# Connector_Card2.net
KiCad netlist of a schematic drawn in Altium Designer
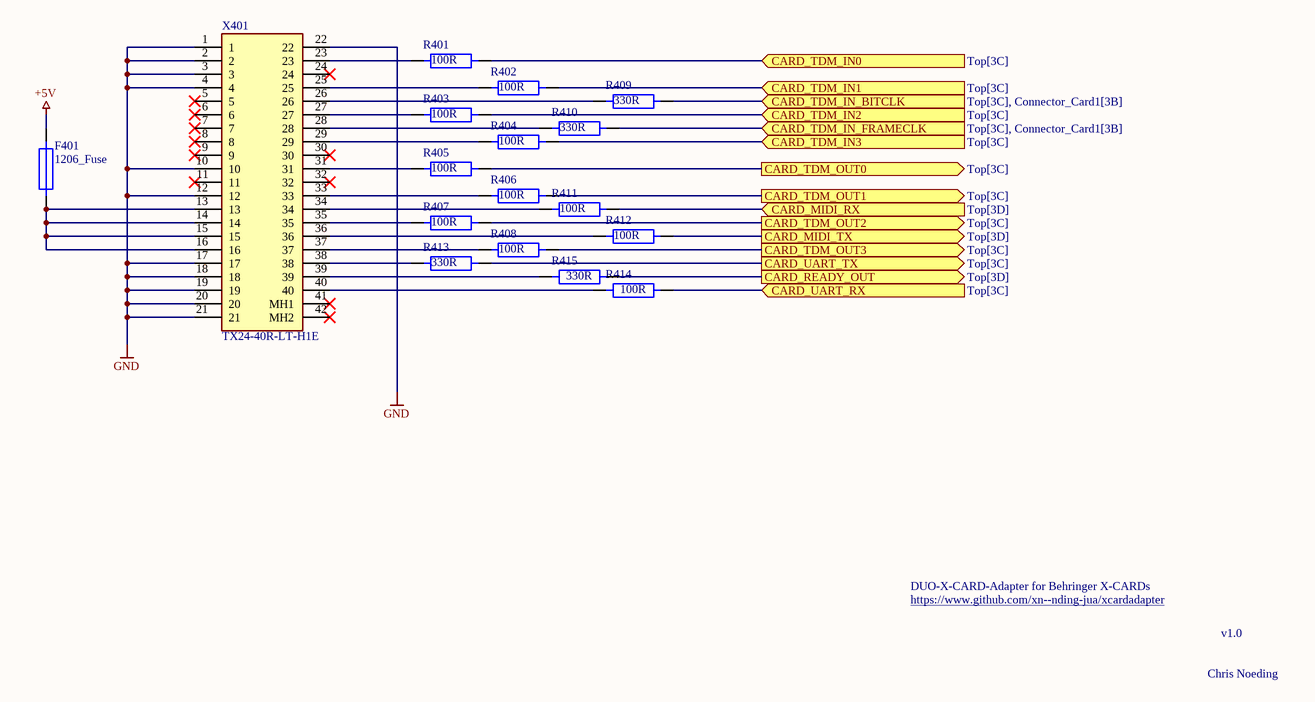
[diagram p0: Connector_Card2.SchDoc]

(export (version "E")
  (design (tool "Eeschema 10.0.6"))
  (components
    (comp (ref "F401")
      (value "1206_Fuse")
      (footprint "1206")
      (libsource (lib "FPGA_Board_Library") (part "1206_Fuse"))
    )
    (comp (ref "R401")
      (value "100R")
      (footprint "1206")
      (description "1206_R")
      (libsource (lib "FPGA_Board_Library") (part "1206_R"))
    )
    (comp (ref "R402")
      (value "100R")
      (footprint "1206")
      (description "1206_R")
      (libsource (lib "FPGA_Board_Library") (part "1206_R"))
    )
    (comp (ref "R403")
      (value "100R")
      (footprint "1206")
      (description "1206_R")
      (libsource (lib "FPGA_Board_Library") (part "1206_R"))
    )
    (comp (ref "R404")
      (value "100R")
      (footprint "1206")
      (description "1206_R")
      (libsource (lib "FPGA_Board_Library") (part "1206_R"))
    )
    (comp (ref "R405")
      (value "100R")
      (footprint "1206")
      (description "330R")
      (libsource (lib "FPGA_Board_Library") (part "1206_R"))
    )
    (comp (ref "R406")
      (value "100R")
      (footprint "1206")
      (description "330R")
      (libsource (lib "FPGA_Board_Library") (part "1206_R"))
    )
    (comp (ref "R407")
      (value "100R")
      (footprint "1206")
      (description "1206_R")
      (libsource (lib "FPGA_Board_Library") (part "1206_R"))
    )
    (comp (ref "R408")
      (value "100R")
      (footprint "1206")
      (description "1206_R")
      (libsource (lib "FPGA_Board_Library") (part "1206_R"))
    )
    (comp (ref "R409")
      (value "330R")
      (footprint "1206")
      (description "1206_R")
      (libsource (lib "FPGA_Board_Library") (part "1206_R"))
    )
    (comp (ref "R410")
      (value "330R")
      (footprint "1206")
      (description "1206_R")
      (libsource (lib "FPGA_Board_Library") (part "1206_R"))
    )
    (comp (ref "R411")
      (value "100R")
      (footprint "1206")
      (description "1206_R")
      (libsource (lib "FPGA_Board_Library") (part "1206_R"))
    )
    (comp (ref "R412")
      (value "100R")
      (footprint "1206")
      (description "1206_R")
      (libsource (lib "FPGA_Board_Library") (part "1206_R"))
    )
    (comp (ref "R413")
      (value "330R")
      (footprint "1206")
      (description "1206_R")
      (libsource (lib "FPGA_Board_Library") (part "1206_R"))
    )
    (comp (ref "R414")
      (value "100R")
      (footprint "1206")
      (description "1206_R")
      (libsource (lib "FPGA_Board_Library") (part "1206_R"))
    )
    (comp (ref "R415")
      (value "330R")
      (footprint "1206")
      (description "1206_R")
      (libsource (lib "FPGA_Board_Library") (part "1206_R"))
    )
    (comp (ref "X401")
      (value "TX24-40R-LT-H1E")
      (footprint "SamacSys:TX2440RLTH1E")
      (description "Connector")
      (fields (field (name "MOUSER PART NUMBER") "656-TX24-40R-LT-H1E"))
      (libsource (lib "*") (part "TX24-40R-LT-H1E"))
    )
  )
  (nets
    (net (code "1") (name "+5V") (class "Default")
      (node (ref "F401") (pin "2") (pinfunction "2_2") (pintype "passive"))
    )
    (net (code "2") (name "/CARD_MIDI_RX") (class "Default")
      (node (ref "R411") (pin "2") (pinfunction "2_2") (pintype "passive"))
    )
    (net (code "3") (name "/CARD_MIDI_TX") (class "Default")
      (node (ref "R412") (pin "2") (pinfunction "2_2") (pintype "passive"))
    )
    (net (code "4") (name "/CARD_READY_OUT") (class "Default")
      (node (ref "R415") (pin "2") (pinfunction "2_2") (pintype "passive"))
    )
    (net (code "5") (name "/CARD_TDM_IN0") (class "Default")
      (node (ref "R401") (pin "2") (pinfunction "2_2") (pintype "passive"))
    )
    (net (code "6") (name "/CARD_TDM_IN1") (class "Default")
      (node (ref "R402") (pin "2") (pinfunction "2_2") (pintype "passive"))
    )
    (net (code "7") (name "/CARD_TDM_IN2") (class "Default")
      (node (ref "R403") (pin "2") (pinfunction "2_2") (pintype "passive"))
    )
    (net (code "8") (name "/CARD_TDM_IN3") (class "Default")
      (node (ref "R404") (pin "2") (pinfunction "2_2") (pintype "passive"))
    )
    (net (code "9") (name "/CARD_TDM_IN_BITCLK") (class "Default")
      (node (ref "R409") (pin "2") (pinfunction "2_2") (pintype "passive"))
    )
    (net (code "10") (name "/CARD_TDM_IN_FRAMECLK") (class "Default")
      (node (ref "R410") (pin "2") (pinfunction "2_2") (pintype "passive"))
    )
    (net (code "11") (name "/CARD_TDM_OUT0") (class "Default")
      (node (ref "R405") (pin "2") (pinfunction "2_2") (pintype "passive"))
    )
    (net (code "12") (name "/CARD_TDM_OUT1") (class "Default")
      (node (ref "R406") (pin "2") (pinfunction "2_2") (pintype "passive"))
    )
    (net (code "13") (name "/CARD_TDM_OUT2") (class "Default")
      (node (ref "R407") (pin "2") (pinfunction "2_2") (pintype "passive"))
    )
    (net (code "14") (name "/CARD_TDM_OUT3") (class "Default")
      (node (ref "R408") (pin "2") (pinfunction "2_2") (pintype "passive"))
    )
    (net (code "15") (name "/CARD_UART_RX") (class "Default")
      (node (ref "R414") (pin "2") (pinfunction "2_2") (pintype "passive"))
    )
    (net (code "16") (name "/CARD_UART_TX") (class "Default")
      (node (ref "R413") (pin "2") (pinfunction "2_2") (pintype "passive"))
    )
    (net (code "17") (name "GND") (class "Default")
      (node (ref "X401") (pin "1") (pinfunction "1_1") (pintype "passive"))
      (node (ref "X401") (pin "10") (pinfunction "10_10") (pintype "passive"))
      (node (ref "X401") (pin "12") (pinfunction "12_12") (pintype "passive"))
      (node (ref "X401") (pin "17") (pinfunction "17_17") (pintype "passive"))
      (node (ref "X401") (pin "18") (pinfunction "18_18") (pintype "passive"))
      (node (ref "X401") (pin "19") (pinfunction "19_19") (pintype "passive"))
      (node (ref "X401") (pin "2") (pinfunction "2_2") (pintype "passive"))
      (node (ref "X401") (pin "20") (pinfunction "20_20") (pintype "passive"))
      (node (ref "X401") (pin "21") (pinfunction "21_21") (pintype "passive"))
      (node (ref "X401") (pin "22") (pinfunction "22_22") (pintype "passive"))
      (node (ref "X401") (pin "3") (pinfunction "3_3") (pintype "passive"))
      (node (ref "X401") (pin "4") (pinfunction "4_4") (pintype "passive"))
    )
    (net (code "18") (name "Net-(F401-Pad1)") (class "Default")
      (node (ref "F401") (pin "1") (pinfunction "1_1") (pintype "passive"))
      (node (ref "X401") (pin "13") (pinfunction "13_13") (pintype "passive"))
      (node (ref "X401") (pin "14") (pinfunction "14_14") (pintype "passive"))
      (node (ref "X401") (pin "15") (pinfunction "15_15") (pintype "passive"))
      (node (ref "X401") (pin "16") (pinfunction "16_16") (pintype "passive"))
    )
    (net (code "19") (name "Net-(R401-Pad1)") (class "Default")
      (node (ref "R401") (pin "1") (pinfunction "1_1") (pintype "passive"))
      (node (ref "X401") (pin "23") (pinfunction "23_23") (pintype "passive"))
    )
    (net (code "20") (name "Net-(R402-Pad1)") (class "Default")
      (node (ref "R402") (pin "1") (pinfunction "1_1") (pintype "passive"))
      (node (ref "X401") (pin "25") (pinfunction "25_25") (pintype "passive"))
    )
    (net (code "21") (name "Net-(R403-Pad1)") (class "Default")
      (node (ref "R403") (pin "1") (pinfunction "1_1") (pintype "passive"))
      (node (ref "X401") (pin "27") (pinfunction "27_27") (pintype "passive"))
    )
    (net (code "22") (name "Net-(R404-Pad1)") (class "Default")
      (node (ref "R404") (pin "1") (pinfunction "1_1") (pintype "passive"))
      (node (ref "X401") (pin "29") (pinfunction "29_29") (pintype "passive"))
    )
    (net (code "23") (name "Net-(R405-Pad1)") (class "Default")
      (node (ref "R405") (pin "1") (pinfunction "1_1") (pintype "passive"))
      (node (ref "X401") (pin "31") (pinfunction "31_31") (pintype "passive"))
    )
    (net (code "24") (name "Net-(R406-Pad1)") (class "Default")
      (node (ref "R406") (pin "1") (pinfunction "1_1") (pintype "passive"))
      (node (ref "X401") (pin "33") (pinfunction "33_33") (pintype "passive"))
    )
    (net (code "25") (name "Net-(R407-Pad1)") (class "Default")
      (node (ref "R407") (pin "1") (pinfunction "1_1") (pintype "passive"))
      (node (ref "X401") (pin "35") (pinfunction "35_35") (pintype "passive"))
    )
    (net (code "26") (name "Net-(R408-Pad1)") (class "Default")
      (node (ref "R408") (pin "1") (pinfunction "1_1") (pintype "passive"))
      (node (ref "X401") (pin "37") (pinfunction "37_37") (pintype "passive"))
    )
    (net (code "27") (name "Net-(R409-Pad1)") (class "Default")
      (node (ref "R409") (pin "1") (pinfunction "1_1") (pintype "passive"))
      (node (ref "X401") (pin "26") (pinfunction "26_26") (pintype "passive"))
    )
    (net (code "28") (name "Net-(R410-Pad1)") (class "Default")
      (node (ref "R410") (pin "1") (pinfunction "1_1") (pintype "passive"))
      (node (ref "X401") (pin "28") (pinfunction "28_28") (pintype "passive"))
    )
    (net (code "29") (name "Net-(R411-Pad1)") (class "Default")
      (node (ref "R411") (pin "1") (pinfunction "1_1") (pintype "passive"))
      (node (ref "X401") (pin "34") (pinfunction "34_34") (pintype "passive"))
    )
    (net (code "30") (name "Net-(R412-Pad1)") (class "Default")
      (node (ref "R412") (pin "1") (pinfunction "1_1") (pintype "passive"))
      (node (ref "X401") (pin "36") (pinfunction "36_36") (pintype "passive"))
    )
    (net (code "31") (name "Net-(R413-Pad1)") (class "Default")
      (node (ref "R413") (pin "1") (pinfunction "1_1") (pintype "passive"))
      (node (ref "X401") (pin "38") (pinfunction "38_38") (pintype "passive"))
    )
    (net (code "32") (name "Net-(R414-Pad1)") (class "Default")
      (node (ref "R414") (pin "1") (pinfunction "1_1") (pintype "passive"))
      (node (ref "X401") (pin "40") (pinfunction "40_40") (pintype "passive"))
    )
    (net (code "33") (name "Net-(R415-Pad1)") (class "Default")
      (node (ref "R415") (pin "1") (pinfunction "1_1") (pintype "passive"))
      (node (ref "X401") (pin "39") (pinfunction "39_39") (pintype "passive"))
    )
    (net (code "34") (name "unconnected-(X401-MH1-Pad41)") (class "Default")
      (node (ref "X401") (pin "41") (pinfunction "MH1_41") (pintype "passive+no_connect"))
    )
    (net (code "35") (name "unconnected-(X401-MH2-Pad42)") (class "Default")
      (node (ref "X401") (pin "42") (pinfunction "MH2_42") (pintype "passive+no_connect"))
    )
    (net (code "36") (name "unconnected-(X401-Pad5)") (class "Default")
      (node (ref "X401") (pin "5") (pinfunction "5_5") (pintype "passive+no_connect"))
    )
    (net (code "37") (name "unconnected-(X401-Pad6)") (class "Default")
      (node (ref "X401") (pin "6") (pinfunction "6_6") (pintype "passive+no_connect"))
    )
    (net (code "38") (name "unconnected-(X401-Pad7)") (class "Default")
      (node (ref "X401") (pin "7") (pinfunction "7_7") (pintype "passive+no_connect"))
    )
    (net (code "39") (name "unconnected-(X401-Pad8)") (class "Default")
      (node (ref "X401") (pin "8") (pinfunction "8_8") (pintype "passive+no_connect"))
    )
    (net (code "40") (name "unconnected-(X401-Pad9)") (class "Default")
      (node (ref "X401") (pin "9") (pinfunction "9_9") (pintype "passive+no_connect"))
    )
    (net (code "41") (name "unconnected-(X401-Pad11)") (class "Default")
      (node (ref "X401") (pin "11") (pinfunction "11_11") (pintype "passive+no_connect"))
    )
    (net (code "42") (name "unconnected-(X401-Pad24)") (class "Default")
      (node (ref "X401") (pin "24") (pinfunction "24_24") (pintype "passive+no_connect"))
    )
    (net (code "43") (name "unconnected-(X401-Pad30)") (class "Default")
      (node (ref "X401") (pin "30") (pinfunction "30_30") (pintype "passive+no_connect"))
    )
    (net (code "44") (name "unconnected-(X401-Pad32)") (class "Default")
      (node (ref "X401") (pin "32") (pinfunction "32_32") (pintype "passive+no_connect"))
    )
  )
)
